# SBUS.net
KiCad netlist of a schematic drawn in Altium Designer
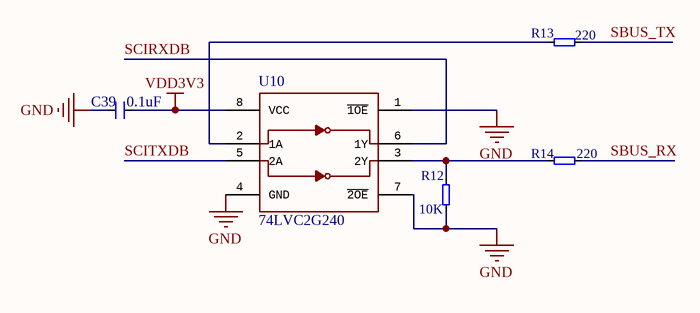
[diagram p0: SBUS.SchDoc]

(export (version "E")
  (design (tool "Eeschema 10.0.6"))
  (components
    (comp (ref "C39") (value "0.1uF") (footprint "0603C") (libsource (lib "研发中心原理图库文件") (part "C")))
    (comp (ref "R12") (value "10K") (footprint "0603R") (libsource (lib "研发中心原理图库文件") (part "R")))
    (comp (ref "R13") (value "220") (footprint "0603R") (libsource (lib "研发中心原理图库文件") (part "R")))
    (comp (ref "R14") (value "220") (footprint "0603R") (libsource (lib "研发中心原理图库文件") (part "R")))
    (comp (ref "U10")
      (value "74LVC2G240")
      (footprint "VSSOP8-0.5")
      (libsource (lib "研发中心原理图库文件") (part "74LVC2G240"))
    )
  )
  (nets
    (net (code "1") (name "/SBUS_RX") (class "Default") (node (ref "R14") (pin "1") (pintype "passive")))
    (net (code "2") (name "/SBUS_TX") (class "Default") (node (ref "R13") (pin "1") (pintype "passive")))
    (net (code "3") (name "/SCIRXDB") (class "Default")
      (node (ref "U10") (pin "6") (pinfunction "1Y_6") (pintype "passive"))
    )
    (net (code "4") (name "/SCITXDB") (class "Default")
      (node (ref "U10") (pin "5") (pinfunction "2A_5") (pintype "passive"))
    )
    (net (code "5") (name "GND") (class "Default")
      (node (ref "C39") (pin "2") (pintype "passive"))
      (node (ref "R12") (pin "2") (pintype "passive"))
      (node (ref "U10") (pin "1") (pinfunction "~{1OE}_1") (pintype "passive"))
      (node (ref "U10") (pin "4") (pinfunction "GND_4") (pintype "open_emitter"))
      (node (ref "U10") (pin "7") (pinfunction "~{2OE}_7") (pintype "passive"))
    )
    (net (code "6") (name "Net-(U10-1A)") (class "Default")
      (node (ref "R13") (pin "2") (pintype "passive"))
      (node (ref "U10") (pin "2") (pinfunction "1A_2") (pintype "passive"))
    )
    (net (code "7") (name "Net-(U10-2Y)") (class "Default")
      (node (ref "R12") (pin "1") (pintype "passive"))
      (node (ref "R14") (pin "2") (pintype "passive"))
      (node (ref "U10") (pin "3") (pinfunction "2Y_3") (pintype "passive"))
    )
    (net (code "8") (name "VDD3V3") (class "Default")
      (node (ref "C39") (pin "1") (pintype "passive"))
      (node (ref "U10") (pin "8") (pinfunction "VCC_8") (pintype "open_emitter"))
    )
  )
)
